# ptvo_fs.net
KiCad netlist of a schematic drawn in EAGLE
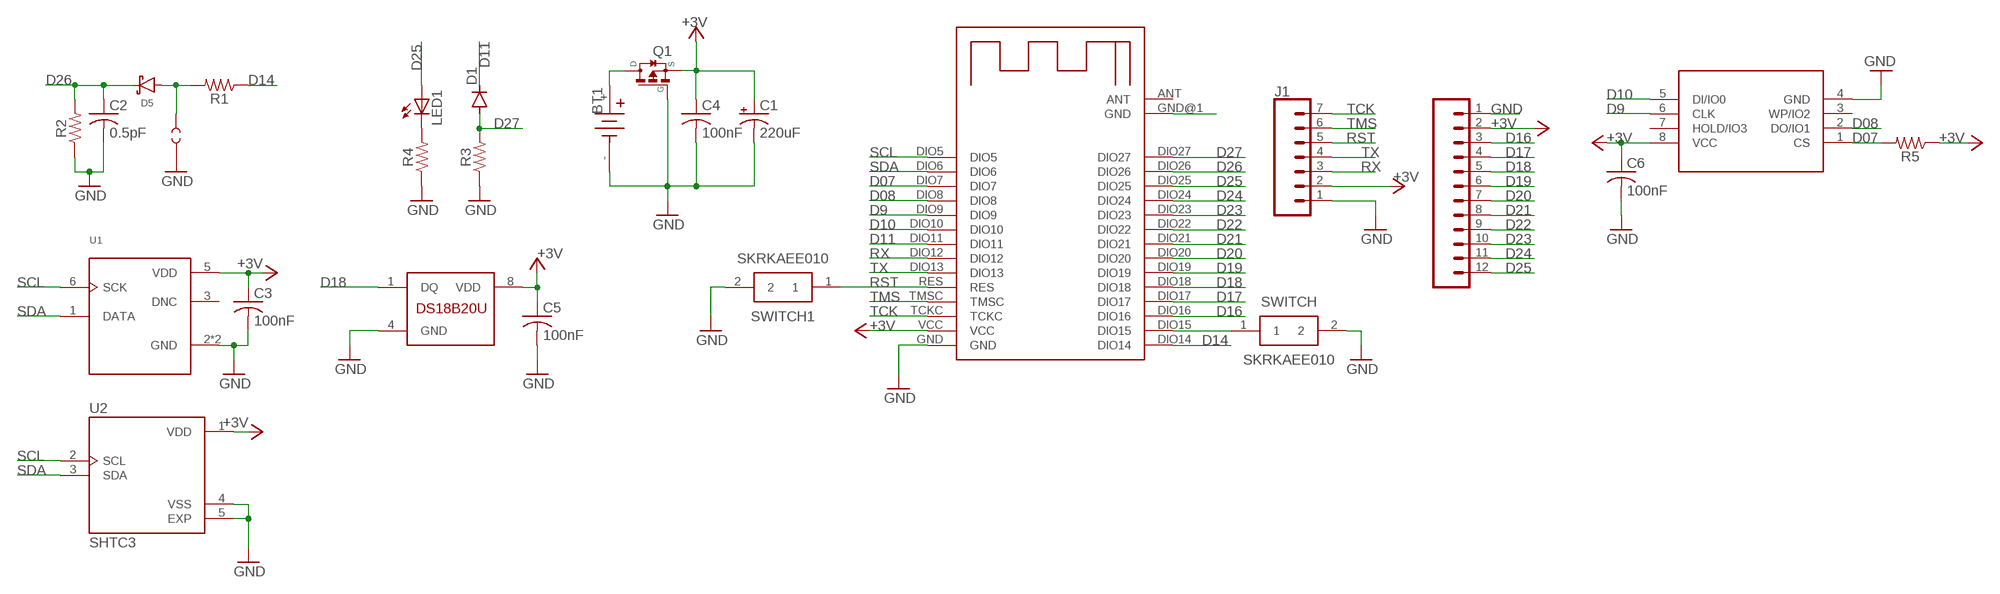
[diagram p0: schematic, sheet 1]

(export (version "E")
  (design (tool "Eeschema 10.0.6"))
  (components
    (comp (ref "BT1")
      (value "BH2AAAPC")
      (footprint "eagle-import:BAT_BH2AAAPC")
      (fields (field (name "MF") "MPD (Memory"))
      (libsource (lib "eagle-import") (part "BH2AAAPC"))
    )
    (comp (ref "C1")
      (value "220uF")
      (footprint "eagle-import:EIA7343")
      (libsource (lib "eagle-import") (part "100UF-POLAR-EIA7343-10V-10%(TANT)"))
    )
    (comp (ref "C2")
      (value "0.5pF")
      (footprint "eagle-import:C0805")
      (libsource (lib "eagle-import") (part "C-USC0805"))
    )
    (comp (ref "C3")
      (value "100nF")
      (footprint "eagle-import:C0805")
      (libsource (lib "eagle-import") (part "C-USC0805"))
    )
    (comp (ref "C4")
      (value "100nF")
      (footprint "eagle-import:C0805")
      (libsource (lib "eagle-import") (part "C-USC0805"))
    )
    (comp (ref "C5")
      (value "100nF")
      (footprint "eagle-import:C0805")
      (libsource (lib "eagle-import") (part "C-USC0805"))
    )
    (comp (ref "C6")
      (value "100nF")
      (footprint "eagle-import:C0805")
      (libsource (lib "eagle-import") (part "C-USC0805"))
    )
    (comp (ref "D1")
      (value "PTSMD3528")
      (footprint "eagle-import:DO214BA")
      (libsource (lib "eagle-import") (part "DIODE-DO214BA"))
    )
    (comp (ref "D5")
      (value "1N4148WS")
      (footprint "eagle-import:SOD-323")
      (libsource (lib "eagle-import") (part "DIODE-SCHOTTKY"))
    )
    (comp (ref "IC1")
      (value "DS18S20USOP8")
      (footprint "eagle-import:UMAX8")
      (libsource (lib "eagle-import") (part "DS18S20USOP8"))
    )
    (comp (ref "J1")
      (value "CONN_051.27MM")
      (footprint "eagle-import:1X05_1.27MM")
      (libsource (lib "eagle-import") (part "SparkFun-Connectors2_CONN_051.27MM"))
    )
    (comp (ref "J2")
      (value "CONN_051.27MM")
      (footprint "eagle-import:1X05_1.27MM")
      (libsource (lib "eagle-import") (part "CONN_051.27MM"))
    )
    (comp (ref "LED1")
      (value "LEDCHIP-LED0805")
      (footprint "eagle-import:CHIP-LED0805")
      (libsource (lib "eagle-import") (part "LEDCHIP-LED0805"))
    )
    (comp (ref "Q1")
      (value "SI2323DS")
      (footprint "eagle-import:SOT23")
      (fields (field (name "MF") "Vishay Siliconix"))
      (libsource (lib "eagle-import") (part "SI2323DS"))
    )
    (comp (ref "R1")
      (value "10k")
      (footprint "eagle-import:M0805")
      (libsource (lib "eagle-import") (part "R-US_M0805"))
    )
    (comp (ref "R2")
      (value "1M")
      (footprint "eagle-import:M0805")
      (libsource (lib "eagle-import") (part "R-US_M0805"))
    )
    (comp (ref "R3")
      (value "10k")
      (footprint "eagle-import:M0805")
      (libsource (lib "eagle-import") (part "R-US_M0805"))
    )
    (comp (ref "R4")
      (value "2.2k")
      (footprint "eagle-import:M0805")
      (libsource (lib "eagle-import") (part "R-US_M0805"))
    )
    (comp (ref "R5")
      (value "2.2k")
      (footprint "eagle-import:M0805")
      (libsource (lib "eagle-import") (part "R-US_M0805"))
    )
    (comp (ref "SWITCH")
      (value "SKRKAEE010")
      (footprint "eagle-import:SKRK")
      (fields (field (name "MF") "ALPS"))
      (libsource (lib "eagle-import") (part "SKRKAEE010"))
    )
    (comp (ref "SWITCH1")
      (value "SKRKAEE010")
      (footprint "eagle-import:SKRK")
      (fields (field (name "MF") "ALPS"))
      (libsource (lib "eagle-import") (part "SKRKAEE010"))
    )
    (comp (ref "TP1")
      (value "TEST-POINT2")
      (footprint "eagle-import:PAD.02X.02")
      (libsource (lib "eagle-import") (part "TEST-POINT2"))
    )
    (comp (ref "TP2")
      (value "TEST-POINT2")
      (footprint "eagle-import:PAD.02X.02")
      (libsource (lib "eagle-import") (part "TEST-POINT2"))
    )
    (comp (ref "U$1")
      (value "RF-BM-2652P2")
      (footprint "eagle-import:RF-BM-2652P2")
      (libsource (lib "eagle-import") (part "RF-BM-2652P2"))
    )
    (comp (ref "U$2")
      (value "IS25LP080D")
      (footprint "eagle-import:SO-8")
      (fields (field (name "MF") "Winbond Electronics") (field (name "MP") "W25Q80BVSNIG"))
      (libsource (lib "eagle-import") (part "W25Q80BVSNIG"))
    )
    (comp (ref "U1")
      (value "HTU21D")
      (footprint "eagle-import:QFN100P300X300X100-7N")
      (fields (field (name "COMMENT") "CAT-HSC0004") (field (name "MF") "TE Connectivity"))
      (libsource (lib "eagle-import") (part "HTU21D"))
    )
    (comp (ref "U2")
      (value "SHTC3")
      (footprint "eagle-import:SON100P200X200X80-5N")
      (fields (field (name "MF") "Sensirion AG"))
      (libsource (lib "eagle-import") (part "SHTC3"))
    )
  )
  (nets
    (net (code "1") (name "+3V") (class "Default")
      (node (ref "C1") (pin "A") (pinfunction "+_A") (pintype "passive"))
      (node (ref "C3") (pin "1") (pinfunction "1_1") (pintype "passive"))
      (node (ref "C4") (pin "1") (pinfunction "1_1") (pintype "passive"))
      (node (ref "C5") (pin "1") (pinfunction "1_1") (pintype "passive"))
      (node (ref "C6") (pin "1") (pinfunction "1_1") (pintype "passive"))
      (node (ref "IC1") (pin "8") (pinfunction "VDD_8") (pintype "power_in"))
      (node (ref "J1") (pin "2") (pinfunction "2_2") (pintype "passive"))
      (node (ref "J2") (pin "2") (pinfunction "2_2") (pintype "passive"))
      (node (ref "Q1") (pin "2") (pinfunction "S_2") (pintype "passive"))
      (node (ref "R5") (pin "1") (pinfunction "1_1") (pintype "passive"))
      (node (ref "U$1") (pin "VCC") (pinfunction "VCC_VCC") (pintype "bidirectional"))
      (node (ref "U$2") (pin "8") (pinfunction "VCC_8") (pintype "bidirectional"))
      (node (ref "U1") (pin "5") (pinfunction "VDD_5") (pintype "power_in"))
      (node (ref "U2") (pin "1") (pinfunction "VDD_1") (pintype "power_in"))
    )
    (net (code "2") (name "/D07") (class "Default")
      (node (ref "R5") (pin "2") (pinfunction "2_2") (pintype "passive"))
      (node (ref "U$1") (pin "DIO7") (pinfunction "DIO7_DIO7") (pintype "bidirectional"))
      (node (ref "U$2") (pin "1") (pinfunction "CS_1") (pintype "bidirectional"))
    )
    (net (code "3") (name "/D08") (class "Default")
      (node (ref "U$1") (pin "DIO8") (pinfunction "DIO8_DIO8") (pintype "bidirectional"))
      (node (ref "U$2") (pin "2") (pinfunction "DO/IO1_2") (pintype "bidirectional"))
    )
    (net (code "4") (name "/D9") (class "Default")
      (node (ref "U$1") (pin "DIO9") (pinfunction "DIO9_DIO9") (pintype "bidirectional"))
      (node (ref "U$2") (pin "6") (pinfunction "CLK_6") (pintype "bidirectional"))
    )
    (net (code "5") (name "/D10") (class "Default")
      (node (ref "U$1") (pin "DIO10") (pinfunction "DIO10_DIO10") (pintype "bidirectional"))
      (node (ref "U$2") (pin "5") (pinfunction "DI/IO0_5") (pintype "bidirectional"))
    )
    (net (code "6") (name "/D11") (class "Default")
      (node (ref "D1") (pin "C") (pinfunction "C_C") (pintype "passive"))
      (node (ref "U$1") (pin "DIO11") (pinfunction "DIO11_DIO11") (pintype "bidirectional"))
    )
    (net (code "7") (name "/D14") (class "Default")
      (node (ref "R1") (pin "1") (pinfunction "1_1") (pintype "passive"))
      (node (ref "U$1") (pin "DIO14") (pinfunction "DIO14_DIO14") (pintype "bidirectional"))
    )
    (net (code "8") (name "/D16") (class "Default")
      (node (ref "J2") (pin "3") (pinfunction "3_3") (pintype "passive"))
      (node (ref "U$1") (pin "DIO16") (pinfunction "DIO16_DIO16") (pintype "bidirectional"))
    )
    (net (code "9") (name "/D17") (class "Default")
      (node (ref "J2") (pin "4") (pinfunction "4_4") (pintype "passive"))
      (node (ref "U$1") (pin "DIO17") (pinfunction "DIO17_DIO17") (pintype "bidirectional"))
    )
    (net (code "10") (name "/D18") (class "Default")
      (node (ref "IC1") (pin "1") (pinfunction "DQ_1") (pintype "bidirectional"))
      (node (ref "J2") (pin "5") (pinfunction "5_5") (pintype "passive"))
      (node (ref "U$1") (pin "DIO18") (pinfunction "DIO18_DIO18") (pintype "bidirectional"))
    )
    (net (code "11") (name "/D19") (class "Default")
      (node (ref "J2") (pin "6") (pinfunction "6_6") (pintype "passive"))
      (node (ref "U$1") (pin "DIO19") (pinfunction "DIO19_DIO19") (pintype "bidirectional"))
    )
    (net (code "12") (name "/D20") (class "Default")
      (node (ref "J2") (pin "7") (pinfunction "7_7") (pintype "passive"))
      (node (ref "U$1") (pin "DIO20") (pinfunction "DIO20_DIO20") (pintype "bidirectional"))
    )
    (net (code "13") (name "/D21") (class "Default")
      (node (ref "J2") (pin "8") (pinfunction "8_8") (pintype "passive"))
      (node (ref "U$1") (pin "DIO21") (pinfunction "DIO21_DIO21") (pintype "bidirectional"))
    )
    (net (code "14") (name "/D22") (class "Default")
      (node (ref "J2") (pin "9") (pinfunction "9_9") (pintype "passive"))
      (node (ref "U$1") (pin "DIO22") (pinfunction "DIO22_DIO22") (pintype "bidirectional"))
    )
    (net (code "15") (name "/D23") (class "Default")
      (node (ref "J2") (pin "10") (pinfunction "10_10") (pintype "passive"))
      (node (ref "U$1") (pin "DIO23") (pinfunction "DIO23_DIO23") (pintype "bidirectional"))
    )
    (net (code "16") (name "/D24") (class "Default")
      (node (ref "J2") (pin "11") (pinfunction "11_11") (pintype "passive"))
      (node (ref "U$1") (pin "DIO24") (pinfunction "DIO24_DIO24") (pintype "bidirectional"))
    )
    (net (code "17") (name "/D25") (class "Default")
      (node (ref "J2") (pin "12") (pinfunction "12_12") (pintype "passive"))
      (node (ref "LED1") (pin "A") (pinfunction "A_A") (pintype "passive"))
      (node (ref "U$1") (pin "DIO25") (pinfunction "DIO25_DIO25") (pintype "bidirectional"))
    )
    (net (code "18") (name "/D26") (class "Default")
      (node (ref "C2") (pin "1") (pinfunction "1_1") (pintype "passive"))
      (node (ref "D5") (pin "C") (pinfunction "C_C") (pintype "passive"))
      (node (ref "R2") (pin "2") (pinfunction "2_2") (pintype "passive"))
      (node (ref "U$1") (pin "DIO26") (pinfunction "DIO26_DIO26") (pintype "bidirectional"))
    )
    (net (code "19") (name "/D27") (class "Default")
      (node (ref "D1") (pin "A") (pinfunction "A_A") (pintype "passive"))
      (node (ref "R3") (pin "2") (pinfunction "2_2") (pintype "passive"))
      (node (ref "U$1") (pin "DIO27") (pinfunction "DIO27_DIO27") (pintype "bidirectional"))
    )
    (net (code "20") (name "/RST") (class "Default")
      (node (ref "J1") (pin "5") (pinfunction "5_5") (pintype "passive"))
      (node (ref "SWITCH1") (pin "1") (pinfunction "1_1") (pintype "passive"))
      (node (ref "U$1") (pin "RES") (pinfunction "RES_RES") (pintype "bidirectional"))
    )
    (net (code "21") (name "/RX") (class "Default")
      (node (ref "J1") (pin "3") (pinfunction "3_3") (pintype "passive"))
      (node (ref "U$1") (pin "DIO12") (pinfunction "DIO12_DIO12") (pintype "bidirectional"))
    )
    (net (code "22") (name "/SCL") (class "Default")
      (node (ref "U$1") (pin "DIO5") (pinfunction "DIO5_DIO5") (pintype "bidirectional"))
      (node (ref "U1") (pin "6") (pinfunction "SCK_6") (pintype "input"))
      (node (ref "U2") (pin "2") (pinfunction "SCL_2") (pintype "bidirectional"))
    )
    (net (code "23") (name "/SDA") (class "Default")
      (node (ref "U$1") (pin "DIO6") (pinfunction "DIO6_DIO6") (pintype "bidirectional"))
      (node (ref "U1") (pin "1") (pinfunction "DATA_1") (pintype "bidirectional"))
      (node (ref "U2") (pin "3") (pinfunction "SDA_3") (pintype "bidirectional"))
    )
    (net (code "24") (name "/TCK") (class "Default")
      (node (ref "J1") (pin "7") (pinfunction "7_7") (pintype "passive"))
      (node (ref "U$1") (pin "TCKC") (pinfunction "TCKC_TCKC") (pintype "bidirectional"))
    )
    (net (code "25") (name "/TMS") (class "Default")
      (node (ref "J1") (pin "6") (pinfunction "6_6") (pintype "passive"))
      (node (ref "U$1") (pin "TMSC") (pinfunction "TMSC_TMSC") (pintype "bidirectional"))
    )
    (net (code "26") (name "/TX") (class "Default")
      (node (ref "J1") (pin "4") (pinfunction "4_4") (pintype "passive"))
      (node (ref "U$1") (pin "DIO13") (pinfunction "DIO13_DIO13") (pintype "bidirectional"))
    )
    (net (code "27") (name "GND") (class "Default")
      (node (ref "BT1") (pin "-") (pinfunction "-_-") (pintype "passive"))
      (node (ref "C1") (pin "C") (pinfunction "-_C") (pintype "passive"))
      (node (ref "C2") (pin "2") (pinfunction "2_2") (pintype "passive"))
      (node (ref "C3") (pin "2") (pinfunction "2_2") (pintype "passive"))
      (node (ref "C4") (pin "2") (pinfunction "2_2") (pintype "passive"))
      (node (ref "C5") (pin "2") (pinfunction "2_2") (pintype "passive"))
      (node (ref "C6") (pin "2") (pinfunction "2_2") (pintype "passive"))
      (node (ref "IC1") (pin "4") (pinfunction "GND_4") (pintype "power_in"))
      (node (ref "J1") (pin "1") (pinfunction "1_1") (pintype "passive"))
      (node (ref "J2") (pin "1") (pinfunction "1_1") (pintype "passive"))
      (node (ref "Q1") (pin "1") (pinfunction "G_1") (pintype "passive"))
      (node (ref "R2") (pin "1") (pinfunction "1_1") (pintype "passive"))
      (node (ref "R3") (pin "1") (pinfunction "1_1") (pintype "passive"))
      (node (ref "R4") (pin "1") (pinfunction "1_1") (pintype "passive"))
      (node (ref "SWITCH") (pin "2") (pinfunction "2_2") (pintype "passive"))
      (node (ref "SWITCH1") (pin "2") (pinfunction "2_2") (pintype "passive"))
      (node (ref "TP2") (pin "P$1") (pinfunction "1_P$1") (pintype "bidirectional"))
      (node (ref "U$1") (pin "GND") (pinfunction "GND_GND") (pintype "bidirectional"))
      (node (ref "U$2") (pin "4") (pinfunction "GND_4") (pintype "bidirectional"))
      (node (ref "U1") (pin "2") (pinfunction "GND_2") (pintype "passive"))
      (node (ref "U1") (pin "PAD") (pinfunction "GND_PAD") (pintype "passive"))
      (node (ref "U2") (pin "4") (pinfunction "VSS_4") (pintype "power_in"))
      (node (ref "U2") (pin "5") (pinfunction "EXP_5") (pintype "power_in"))
    )
    (net (code "28") (name "Net-(LED1-PadC)") (class "Default")
      (node (ref "LED1") (pin "C") (pinfunction "C_C") (pintype "passive"))
      (node (ref "R4") (pin "2") (pinfunction "2_2") (pintype "passive"))
    )
    (net (code "29") (name "Net-(Q1-D)") (class "Default")
      (node (ref "BT1") (pin "+") (pinfunction "+_+") (pintype "passive"))
      (node (ref "Q1") (pin "3") (pinfunction "D_3") (pintype "passive"))
    )
    (net (code "30") (name "Net-(SWITCH-Pad1)") (class "Default")
      (node (ref "SWITCH") (pin "1") (pinfunction "1_1") (pintype "passive"))
      (node (ref "U$1") (pin "DIO15") (pinfunction "DIO15_DIO15") (pintype "bidirectional"))
    )
    (net (code "31") (name "Net-(TP1-1)") (class "Default")
      (node (ref "D5") (pin "A") (pinfunction "A_A") (pintype "passive"))
      (node (ref "R1") (pin "2") (pinfunction "2_2") (pintype "passive"))
      (node (ref "TP1") (pin "P$1") (pinfunction "1_P$1") (pintype "bidirectional"))
    )
    (net (code "32") (name "unconnected-(U$1-GND-PadGND@1)") (class "Default")
      (node (ref "U$1") (pin "GND@1") (pinfunction "GND_GND@1") (pintype "bidirectional"))
    )
    (net (code "33") (name "unconnected-(U$1-PadANT)") (class "Default")
      (node (ref "U$1") (pin "ANT") (pinfunction "ANT_ANT") (pintype "bidirectional"))
    )
    (net (code "34") (name "unconnected-(U$2-HOLD{slash}IO3-Pad7)") (class "Default")
      (node (ref "U$2") (pin "7") (pinfunction "HOLD/IO3_7") (pintype "bidirectional"))
    )
    (net (code "35") (name "unconnected-(U$2-WP{slash}IO2-Pad3)") (class "Default")
      (node (ref "U$2") (pin "3") (pinfunction "WP/IO2_3") (pintype "bidirectional"))
    )
    (net (code "36") (name "unconnected-(U1-DNC-Pad3)") (class "Default")
      (node (ref "U1") (pin "3") (pinfunction "DNC_3") (pintype "bidirectional"))
    )
  )
)
